# BatteryBalancing.net
KiCad netlist of a schematic drawn in Altium Designer
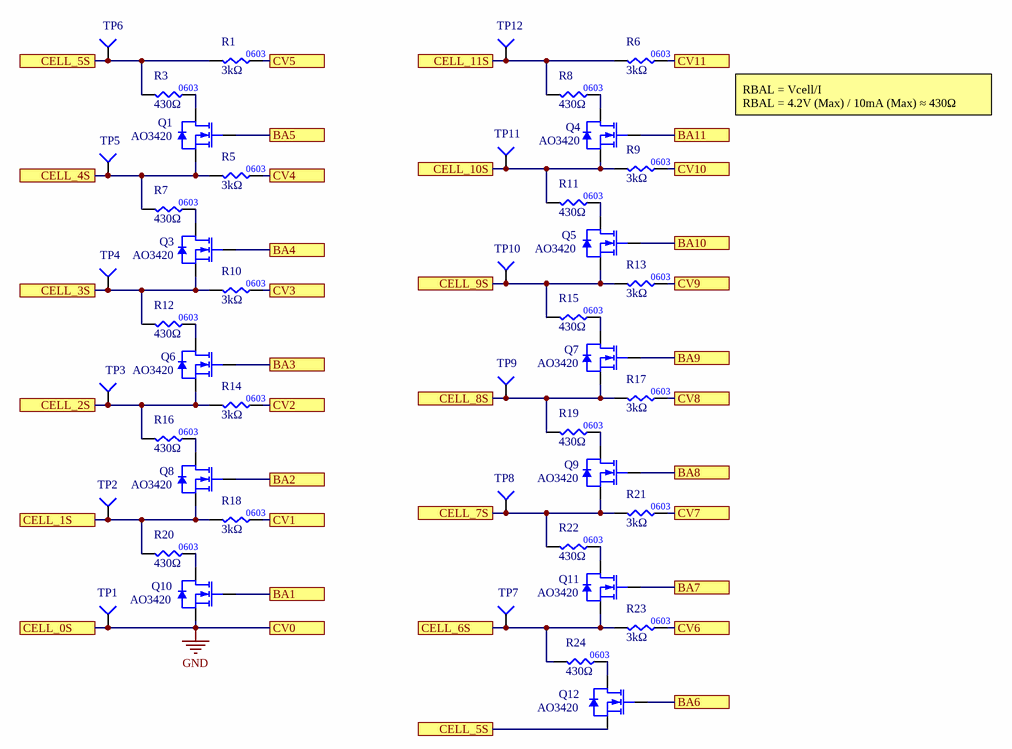
[diagram p0: BatteryBalancing.SchDoc]

(export (version "E")
  (design (tool "Eeschema 10.0.6"))
  (components
    (comp (ref "Q1")
      (value "NMOS_20V_6A")
      (footprint "SOT23-3")
      (description "MOSFET N-CH 20V 6A SOT-23")
      (fields (field (name "MANUFACTURER PART NUMBER 1") "AO3420"))
      (libsource (lib "UWRT_Schematic_Library_2020") (part "NMOS_20V_6A"))
    )
    (comp (ref "Q3")
      (value "NMOS_20V_6A")
      (footprint "SOT23-3")
      (description "MOSFET N-CH 20V 6A SOT-23")
      (fields (field (name "MANUFACTURER PART NUMBER 1") "AO3420"))
      (libsource (lib "UWRT_Schematic_Library_2020") (part "NMOS_20V_6A"))
    )
    (comp (ref "Q4")
      (value "NMOS_20V_6A")
      (footprint "SOT23-3")
      (description "MOSFET N-CH 20V 6A SOT-23")
      (fields (field (name "MANUFACTURER PART NUMBER 1") "AO3420"))
      (libsource (lib "UWRT_Schematic_Library_2020") (part "NMOS_20V_6A"))
    )
    (comp (ref "Q5")
      (value "NMOS_20V_6A")
      (footprint "SOT23-3")
      (description "MOSFET N-CH 20V 6A SOT-23")
      (fields (field (name "MANUFACTURER PART NUMBER 1") "AO3420"))
      (libsource (lib "UWRT_Schematic_Library_2020") (part "NMOS_20V_6A"))
    )
    (comp (ref "Q6")
      (value "NMOS_20V_6A")
      (footprint "SOT23-3")
      (description "MOSFET N-CH 20V 6A SOT-23")
      (fields (field (name "MANUFACTURER PART NUMBER 1") "AO3420"))
      (libsource (lib "UWRT_Schematic_Library_2020") (part "NMOS_20V_6A"))
    )
    (comp (ref "Q7")
      (value "NMOS_20V_6A")
      (footprint "SOT23-3")
      (description "MOSFET N-CH 20V 6A SOT-23")
      (fields (field (name "MANUFACTURER PART NUMBER 1") "AO3420"))
      (libsource (lib "UWRT_Schematic_Library_2020") (part "NMOS_20V_6A"))
    )
    (comp (ref "Q8")
      (value "NMOS_20V_6A")
      (footprint "SOT23-3")
      (description "MOSFET N-CH 20V 6A SOT-23")
      (fields (field (name "MANUFACTURER PART NUMBER 1") "AO3420"))
      (libsource (lib "UWRT_Schematic_Library_2020") (part "NMOS_20V_6A"))
    )
    (comp (ref "Q9")
      (value "NMOS_20V_6A")
      (footprint "SOT23-3")
      (description "MOSFET N-CH 20V 6A SOT-23")
      (fields (field (name "MANUFACTURER PART NUMBER 1") "AO3420"))
      (libsource (lib "UWRT_Schematic_Library_2020") (part "NMOS_20V_6A"))
    )
    (comp (ref "Q10")
      (value "NMOS_20V_6A")
      (footprint "SOT23-3")
      (description "MOSFET N-CH 20V 6A SOT-23")
      (fields (field (name "MANUFACTURER PART NUMBER 1") "AO3420"))
      (libsource (lib "UWRT_Schematic_Library_2020") (part "NMOS_20V_6A"))
    )
    (comp (ref "Q11")
      (value "NMOS_20V_6A")
      (footprint "SOT23-3")
      (description "MOSFET N-CH 20V 6A SOT-23")
      (fields (field (name "MANUFACTURER PART NUMBER 1") "AO3420"))
      (libsource (lib "UWRT_Schematic_Library_2020") (part "NMOS_20V_6A"))
    )
    (comp (ref "Q12")
      (value "NMOS_20V_6A")
      (footprint "SOT23-3")
      (description "MOSFET N-CH 20V 6A SOT-23")
      (fields (field (name "MANUFACTURER PART NUMBER 1") "AO3420"))
      (libsource (lib "UWRT_Schematic_Library_2020") (part "NMOS_20V_6A"))
    )
    (comp (ref "R1")
      (value "3kΩ")
      (footprint "RES0603")
      (description "RES 3K OHM 1% 1/10W 0603")
      (fields (field (name "Comment") "RES_3kΩ_0603_1%"))
      (libsource (lib "UWRT_Schematic_Library_2020") (part "RES_3kΩ_0603_1%"))
    )
    (comp (ref "R3")
      (value "430Ω")
      (footprint "RES0603")
      (description "RES 430 OHM 5% 1/10W 0603")
      (fields (field (name "Comment") "RES_430Ω_0603_5%"))
      (libsource (lib "UWRT_Schematic_Library_2020") (part "RES_430Ω_0603_5%"))
    )
    (comp (ref "R5")
      (value "3kΩ")
      (footprint "RES0603")
      (description "RES 3K OHM 1% 1/10W 0603")
      (fields (field (name "Comment") "RES_3kΩ_0603_1%"))
      (libsource (lib "UWRT_Schematic_Library_2020") (part "RES_3kΩ_0603_1%"))
    )
    (comp (ref "R6")
      (value "3kΩ")
      (footprint "RES0603")
      (description "RES 3K OHM 1% 1/10W 0603")
      (fields (field (name "Comment") "RES_3kΩ_0603_1%"))
      (libsource (lib "UWRT_Schematic_Library_2020") (part "RES_3kΩ_0603_1%"))
    )
    (comp (ref "R7")
      (value "430Ω")
      (footprint "RES0603")
      (description "RES 430 OHM 5% 1/10W 0603")
      (fields (field (name "Comment") "RES_430Ω_0603_5%"))
      (libsource (lib "UWRT_Schematic_Library_2020") (part "RES_430Ω_0603_5%"))
    )
    (comp (ref "R8")
      (value "430Ω")
      (footprint "RES0603")
      (description "RES 430 OHM 5% 1/10W 0603")
      (fields (field (name "Comment") "RES_430Ω_0603_5%"))
      (libsource (lib "UWRT_Schematic_Library_2020") (part "RES_430Ω_0603_5%"))
    )
    (comp (ref "R9")
      (value "3kΩ")
      (footprint "RES0603")
      (description "RES 3K OHM 1% 1/10W 0603")
      (fields (field (name "Comment") "RES_3kΩ_0603_1%"))
      (libsource (lib "UWRT_Schematic_Library_2020") (part "RES_3kΩ_0603_1%"))
    )
    (comp (ref "R10")
      (value "3kΩ")
      (footprint "RES0603")
      (description "RES 3K OHM 1% 1/10W 0603")
      (fields (field (name "Comment") "RES_3kΩ_0603_1%"))
      (libsource (lib "UWRT_Schematic_Library_2020") (part "RES_3kΩ_0603_1%"))
    )
    (comp (ref "R11")
      (value "430Ω")
      (footprint "RES0603")
      (description "RES 430 OHM 5% 1/10W 0603")
      (fields (field (name "Comment") "RES_430Ω_0603_5%"))
      (libsource (lib "UWRT_Schematic_Library_2020") (part "RES_430Ω_0603_5%"))
    )
    (comp (ref "R12")
      (value "430Ω")
      (footprint "RES0603")
      (description "RES 430 OHM 5% 1/10W 0603")
      (fields (field (name "Comment") "RES_430Ω_0603_5%"))
      (libsource (lib "UWRT_Schematic_Library_2020") (part "RES_430Ω_0603_5%"))
    )
    (comp (ref "R13")
      (value "3kΩ")
      (footprint "RES0603")
      (description "RES 3K OHM 1% 1/10W 0603")
      (fields (field (name "Comment") "RES_3kΩ_0603_1%"))
      (libsource (lib "UWRT_Schematic_Library_2020") (part "RES_3kΩ_0603_1%"))
    )
    (comp (ref "R14")
      (value "3kΩ")
      (footprint "RES0603")
      (description "RES 3K OHM 1% 1/10W 0603")
      (fields (field (name "Comment") "RES_3kΩ_0603_1%"))
      (libsource (lib "UWRT_Schematic_Library_2020") (part "RES_3kΩ_0603_1%"))
    )
    (comp (ref "R15")
      (value "430Ω")
      (footprint "RES0603")
      (description "RES 430 OHM 5% 1/10W 0603")
      (fields (field (name "Comment") "RES_430Ω_0603_5%"))
      (libsource (lib "UWRT_Schematic_Library_2020") (part "RES_430Ω_0603_5%"))
    )
    (comp (ref "R16")
      (value "430Ω")
      (footprint "RES0603")
      (description "RES 430 OHM 5% 1/10W 0603")
      (fields (field (name "Comment") "RES_430Ω_0603_5%"))
      (libsource (lib "UWRT_Schematic_Library_2020") (part "RES_430Ω_0603_5%"))
    )
    (comp (ref "R17")
      (value "3kΩ")
      (footprint "RES0603")
      (description "RES 3K OHM 1% 1/10W 0603")
      (fields (field (name "Comment") "RES_3kΩ_0603_1%"))
      (libsource (lib "UWRT_Schematic_Library_2020") (part "RES_3kΩ_0603_1%"))
    )
    (comp (ref "R18")
      (value "3kΩ")
      (footprint "RES0603")
      (description "RES 3K OHM 1% 1/10W 0603")
      (fields (field (name "Comment") "RES_3kΩ_0603_1%"))
      (libsource (lib "UWRT_Schematic_Library_2020") (part "RES_3kΩ_0603_1%"))
    )
    (comp (ref "R19")
      (value "430Ω")
      (footprint "RES0603")
      (description "RES 430 OHM 5% 1/10W 0603")
      (fields (field (name "Comment") "RES_430Ω_0603_5%"))
      (libsource (lib "UWRT_Schematic_Library_2020") (part "RES_430Ω_0603_5%"))
    )
    (comp (ref "R20")
      (value "430Ω")
      (footprint "RES0603")
      (description "RES 430 OHM 5% 1/10W 0603")
      (fields (field (name "Comment") "RES_430Ω_0603_5%"))
      (libsource (lib "UWRT_Schematic_Library_2020") (part "RES_430Ω_0603_5%"))
    )
    (comp (ref "R21")
      (value "3kΩ")
      (footprint "RES0603")
      (description "RES 3K OHM 1% 1/10W 0603")
      (fields (field (name "Comment") "RES_3kΩ_0603_1%"))
      (libsource (lib "UWRT_Schematic_Library_2020") (part "RES_3kΩ_0603_1%"))
    )
    (comp (ref "R22")
      (value "430Ω")
      (footprint "RES0603")
      (description "RES 430 OHM 5% 1/10W 0603")
      (fields (field (name "Comment") "RES_430Ω_0603_5%"))
      (libsource (lib "UWRT_Schematic_Library_2020") (part "RES_430Ω_0603_5%"))
    )
    (comp (ref "R23")
      (value "3kΩ")
      (footprint "RES0603")
      (description "RES 3K OHM 1% 1/10W 0603")
      (fields (field (name "Comment") "RES_3kΩ_0603_1%"))
      (libsource (lib "UWRT_Schematic_Library_2020") (part "RES_3kΩ_0603_1%"))
    )
    (comp (ref "R24")
      (value "430Ω")
      (footprint "RES0603")
      (description "RES 430 OHM 5% 1/10W 0603")
      (fields (field (name "Comment") "RES_430Ω_0603_5%"))
      (libsource (lib "UWRT_Schematic_Library_2020") (part "RES_430Ω_0603_5%"))
    )
    (comp (ref "TP1")
      (value "TESTPOINT_1MM_SQUARE")
      (footprint "TESTPOINT_SQUARE_1MM")
      (description "CELL0")
      (libsource (lib "UWRT_Schematic_Library_2020") (part "TESTPOINT_1MM_SQUARE"))
    )
    (comp (ref "TP2")
      (value "TESTPOINT_1MM_SQUARE")
      (footprint "TESTPOINT_SQUARE_1MM")
      (description "CELL1")
      (libsource (lib "UWRT_Schematic_Library_2020") (part "TESTPOINT_1MM_SQUARE"))
    )
    (comp (ref "TP3")
      (value "TESTPOINT_1MM_SQUARE")
      (footprint "TESTPOINT_SQUARE_1MM")
      (description "CELL2")
      (libsource (lib "UWRT_Schematic_Library_2020") (part "TESTPOINT_1MM_SQUARE"))
    )
    (comp (ref "TP4")
      (value "TESTPOINT_1MM_SQUARE")
      (footprint "TESTPOINT_SQUARE_1MM")
      (description "CELL3")
      (libsource (lib "UWRT_Schematic_Library_2020") (part "TESTPOINT_1MM_SQUARE"))
    )
    (comp (ref "TP5")
      (value "TESTPOINT_1MM_SQUARE")
      (footprint "TESTPOINT_SQUARE_1MM")
      (description "CELL4")
      (libsource (lib "UWRT_Schematic_Library_2020") (part "TESTPOINT_1MM_SQUARE"))
    )
    (comp (ref "TP6")
      (value "TESTPOINT_1MM_SQUARE")
      (footprint "TESTPOINT_SQUARE_1MM")
      (description "CELL5")
      (libsource (lib "UWRT_Schematic_Library_2020") (part "TESTPOINT_1MM_SQUARE"))
    )
    (comp (ref "TP7")
      (value "TESTPOINT_1MM_SQUARE")
      (footprint "TESTPOINT_SQUARE_1MM")
      (description "CELL6")
      (libsource (lib "UWRT_Schematic_Library_2020") (part "TESTPOINT_1MM_SQUARE"))
    )
    (comp (ref "TP8")
      (value "TESTPOINT_1MM_SQUARE")
      (footprint "TESTPOINT_SQUARE_1MM")
      (description "CELL7")
      (libsource (lib "UWRT_Schematic_Library_2020") (part "TESTPOINT_1MM_SQUARE"))
    )
    (comp (ref "TP9")
      (value "TESTPOINT_1MM_SQUARE")
      (footprint "TESTPOINT_SQUARE_1MM")
      (description "CELL8")
      (libsource (lib "UWRT_Schematic_Library_2020") (part "TESTPOINT_1MM_SQUARE"))
    )
    (comp (ref "TP10")
      (value "TESTPOINT_1MM_SQUARE")
      (footprint "TESTPOINT_SQUARE_1MM")
      (description "CELL9")
      (libsource (lib "UWRT_Schematic_Library_2020") (part "TESTPOINT_1MM_SQUARE"))
    )
    (comp (ref "TP11")
      (value "TESTPOINT_1MM_SQUARE")
      (footprint "TESTPOINT_SQUARE_1MM")
      (description "CELL10")
      (libsource (lib "UWRT_Schematic_Library_2020") (part "TESTPOINT_1MM_SQUARE"))
    )
    (comp (ref "TP12")
      (value "TESTPOINT_1MM_SQUARE")
      (footprint "TESTPOINT_SQUARE_1MM")
      (description "CELL11")
      (libsource (lib "UWRT_Schematic_Library_2020") (part "TESTPOINT_1MM_SQUARE"))
    )
  )
  (nets
    (net (code "1") (name "/BA1") (class "Default")
      (node (ref "Q10") (pin "1") (pinfunction "GATE_1") (pintype "passive"))
    )
    (net (code "2") (name "/BA2") (class "Default")
      (node (ref "Q8") (pin "1") (pinfunction "GATE_1") (pintype "passive"))
    )
    (net (code "3") (name "/BA3") (class "Default")
      (node (ref "Q6") (pin "1") (pinfunction "GATE_1") (pintype "passive"))
    )
    (net (code "4") (name "/BA4") (class "Default")
      (node (ref "Q3") (pin "1") (pinfunction "GATE_1") (pintype "passive"))
    )
    (net (code "5") (name "/BA5") (class "Default")
      (node (ref "Q1") (pin "1") (pinfunction "GATE_1") (pintype "passive"))
    )
    (net (code "6") (name "/BA6") (class "Default")
      (node (ref "Q12") (pin "1") (pinfunction "GATE_1") (pintype "passive"))
    )
    (net (code "7") (name "/BA7") (class "Default")
      (node (ref "Q11") (pin "1") (pinfunction "GATE_1") (pintype "passive"))
    )
    (net (code "8") (name "/BA8") (class "Default")
      (node (ref "Q9") (pin "1") (pinfunction "GATE_1") (pintype "passive"))
    )
    (net (code "9") (name "/BA9") (class "Default")
      (node (ref "Q7") (pin "1") (pinfunction "GATE_1") (pintype "passive"))
    )
    (net (code "10") (name "/BA10") (class "Default")
      (node (ref "Q5") (pin "1") (pinfunction "GATE_1") (pintype "passive"))
    )
    (net (code "11") (name "/BA11") (class "Default")
      (node (ref "Q4") (pin "1") (pinfunction "GATE_1") (pintype "passive"))
    )
    (net (code "12") (name "/CELL_1S") (class "Default")
      (node (ref "Q8") (pin "2") (pinfunction "SOURCE_2") (pintype "passive"))
      (node (ref "R18") (pin "1") (pinfunction "1_1") (pintype "passive"))
      (node (ref "R20") (pin "1") (pinfunction "1_1") (pintype "passive"))
      (node (ref "TP2") (pin "1") (pinfunction "=value_1") (pintype "passive"))
    )
    (net (code "13") (name "/CELL_2S") (class "Default")
      (node (ref "Q6") (pin "2") (pinfunction "SOURCE_2") (pintype "passive"))
      (node (ref "R14") (pin "1") (pinfunction "1_1") (pintype "passive"))
      (node (ref "R16") (pin "1") (pinfunction "1_1") (pintype "passive"))
      (node (ref "TP3") (pin "1") (pinfunction "=value_1") (pintype "passive"))
    )
    (net (code "14") (name "/CELL_3S") (class "Default")
      (node (ref "Q3") (pin "2") (pinfunction "SOURCE_2") (pintype "passive"))
      (node (ref "R10") (pin "1") (pinfunction "1_1") (pintype "passive"))
      (node (ref "R12") (pin "1") (pinfunction "1_1") (pintype "passive"))
      (node (ref "TP4") (pin "1") (pinfunction "=value_1") (pintype "passive"))
    )
    (net (code "15") (name "/CELL_4S") (class "Default")
      (node (ref "Q1") (pin "2") (pinfunction "SOURCE_2") (pintype "passive"))
      (node (ref "R5") (pin "1") (pinfunction "1_1") (pintype "passive"))
      (node (ref "R7") (pin "1") (pinfunction "1_1") (pintype "passive"))
      (node (ref "TP5") (pin "1") (pinfunction "=value_1") (pintype "passive"))
    )
    (net (code "16") (name "/CELL_5S") (class "Default")
      (node (ref "Q12") (pin "2") (pinfunction "SOURCE_2") (pintype "passive"))
      (node (ref "R1") (pin "1") (pinfunction "1_1") (pintype "passive"))
      (node (ref "R3") (pin "1") (pinfunction "1_1") (pintype "passive"))
      (node (ref "TP6") (pin "1") (pinfunction "=value_1") (pintype "passive"))
    )
    (net (code "17") (name "/CELL_6S") (class "Default")
      (node (ref "Q11") (pin "2") (pinfunction "SOURCE_2") (pintype "passive"))
      (node (ref "R23") (pin "1") (pinfunction "1_1") (pintype "passive"))
      (node (ref "R24") (pin "1") (pinfunction "1_1") (pintype "passive"))
      (node (ref "TP7") (pin "1") (pinfunction "=value_1") (pintype "passive"))
    )
    (net (code "18") (name "/CELL_7S") (class "Default")
      (node (ref "Q9") (pin "2") (pinfunction "SOURCE_2") (pintype "passive"))
      (node (ref "R21") (pin "1") (pinfunction "1_1") (pintype "passive"))
      (node (ref "R22") (pin "1") (pinfunction "1_1") (pintype "passive"))
      (node (ref "TP8") (pin "1") (pinfunction "=value_1") (pintype "passive"))
    )
    (net (code "19") (name "/CELL_8S") (class "Default")
      (node (ref "Q7") (pin "2") (pinfunction "SOURCE_2") (pintype "passive"))
      (node (ref "R17") (pin "1") (pinfunction "1_1") (pintype "passive"))
      (node (ref "R19") (pin "1") (pinfunction "1_1") (pintype "passive"))
      (node (ref "TP9") (pin "1") (pinfunction "=value_1") (pintype "passive"))
    )
    (net (code "20") (name "/CELL_9S") (class "Default")
      (node (ref "Q5") (pin "2") (pinfunction "SOURCE_2") (pintype "passive"))
      (node (ref "R13") (pin "1") (pinfunction "1_1") (pintype "passive"))
      (node (ref "R15") (pin "1") (pinfunction "1_1") (pintype "passive"))
      (node (ref "TP10") (pin "1") (pinfunction "=value_1") (pintype "passive"))
    )
    (net (code "21") (name "/CELL_10S") (class "Default")
      (node (ref "Q4") (pin "2") (pinfunction "SOURCE_2") (pintype "passive"))
      (node (ref "R11") (pin "1") (pinfunction "1_1") (pintype "passive"))
      (node (ref "R9") (pin "1") (pinfunction "1_1") (pintype "passive"))
      (node (ref "TP11") (pin "1") (pinfunction "=value_1") (pintype "passive"))
    )
    (net (code "22") (name "/CELL_11S") (class "Default")
      (node (ref "R6") (pin "1") (pinfunction "1_1") (pintype "passive"))
      (node (ref "R8") (pin "1") (pinfunction "1_1") (pintype "passive"))
      (node (ref "TP12") (pin "1") (pinfunction "=value_1") (pintype "passive"))
    )
    (net (code "23") (name "/CV1") (class "Default")
      (node (ref "R18") (pin "2") (pinfunction "2_2") (pintype "passive"))
    )
    (net (code "24") (name "/CV2") (class "Default")
      (node (ref "R14") (pin "2") (pinfunction "2_2") (pintype "passive"))
    )
    (net (code "25") (name "/CV3") (class "Default")
      (node (ref "R10") (pin "2") (pinfunction "2_2") (pintype "passive"))
    )
    (net (code "26") (name "/CV4") (class "Default")
      (node (ref "R5") (pin "2") (pinfunction "2_2") (pintype "passive"))
    )
    (net (code "27") (name "/CV5") (class "Default")
      (node (ref "R1") (pin "2") (pinfunction "2_2") (pintype "passive"))
    )
    (net (code "28") (name "/CV6") (class "Default")
      (node (ref "R23") (pin "2") (pinfunction "2_2") (pintype "passive"))
    )
    (net (code "29") (name "/CV7") (class "Default")
      (node (ref "R21") (pin "2") (pinfunction "2_2") (pintype "passive"))
    )
    (net (code "30") (name "/CV8") (class "Default")
      (node (ref "R17") (pin "2") (pinfunction "2_2") (pintype "passive"))
    )
    (net (code "31") (name "/CV9") (class "Default")
      (node (ref "R13") (pin "2") (pinfunction "2_2") (pintype "passive"))
    )
    (net (code "32") (name "/CV10") (class "Default")
      (node (ref "R9") (pin "2") (pinfunction "2_2") (pintype "passive"))
    )
    (net (code "33") (name "/CV11") (class "Default")
      (node (ref "R6") (pin "2") (pinfunction "2_2") (pintype "passive"))
    )
    (net (code "34") (name "GND") (class "Default")
      (node (ref "Q10") (pin "2") (pinfunction "SOURCE_2") (pintype "passive"))
      (node (ref "TP1") (pin "1") (pinfunction "=value_1") (pintype "passive"))
    )
    (net (code "35") (name "Net-(Q1-DRAIN)") (class "Default")
      (node (ref "Q1") (pin "3") (pinfunction "DRAIN_3") (pintype "passive"))
      (node (ref "R3") (pin "2") (pinfunction "2_2") (pintype "passive"))
    )
    (net (code "36") (name "Net-(Q3-DRAIN)") (class "Default")
      (node (ref "Q3") (pin "3") (pinfunction "DRAIN_3") (pintype "passive"))
      (node (ref "R7") (pin "2") (pinfunction "2_2") (pintype "passive"))
    )
    (net (code "37") (name "Net-(Q4-DRAIN)") (class "Default")
      (node (ref "Q4") (pin "3") (pinfunction "DRAIN_3") (pintype "passive"))
      (node (ref "R8") (pin "2") (pinfunction "2_2") (pintype "passive"))
    )
    (net (code "38") (name "Net-(Q5-DRAIN)") (class "Default")
      (node (ref "Q5") (pin "3") (pinfunction "DRAIN_3") (pintype "passive"))
      (node (ref "R11") (pin "2") (pinfunction "2_2") (pintype "passive"))
    )
    (net (code "39") (name "Net-(Q6-DRAIN)") (class "Default")
      (node (ref "Q6") (pin "3") (pinfunction "DRAIN_3") (pintype "passive"))
      (node (ref "R12") (pin "2") (pinfunction "2_2") (pintype "passive"))
    )
    (net (code "40") (name "Net-(Q7-DRAIN)") (class "Default")
      (node (ref "Q7") (pin "3") (pinfunction "DRAIN_3") (pintype "passive"))
      (node (ref "R15") (pin "2") (pinfunction "2_2") (pintype "passive"))
    )
    (net (code "41") (name "Net-(Q8-DRAIN)") (class "Default")
      (node (ref "Q8") (pin "3") (pinfunction "DRAIN_3") (pintype "passive"))
      (node (ref "R16") (pin "2") (pinfunction "2_2") (pintype "passive"))
    )
    (net (code "42") (name "Net-(Q9-DRAIN)") (class "Default")
      (node (ref "Q9") (pin "3") (pinfunction "DRAIN_3") (pintype "passive"))
      (node (ref "R19") (pin "2") (pinfunction "2_2") (pintype "passive"))
    )
    (net (code "43") (name "Net-(Q10-DRAIN)") (class "Default")
      (node (ref "Q10") (pin "3") (pinfunction "DRAIN_3") (pintype "passive"))
      (node (ref "R20") (pin "2") (pinfunction "2_2") (pintype "passive"))
    )
    (net (code "44") (name "Net-(Q11-DRAIN)") (class "Default")
      (node (ref "Q11") (pin "3") (pinfunction "DRAIN_3") (pintype "passive"))
      (node (ref "R22") (pin "2") (pinfunction "2_2") (pintype "passive"))
    )
    (net (code "45") (name "Net-(Q12-DRAIN)") (class "Default")
      (node (ref "Q12") (pin "3") (pinfunction "DRAIN_3") (pintype "passive"))
      (node (ref "R24") (pin "2") (pinfunction "2_2") (pintype "passive"))
    )
  )
)
